# 3-HumiditySensor.net
KiCad netlist of a schematic drawn in Altium Designer
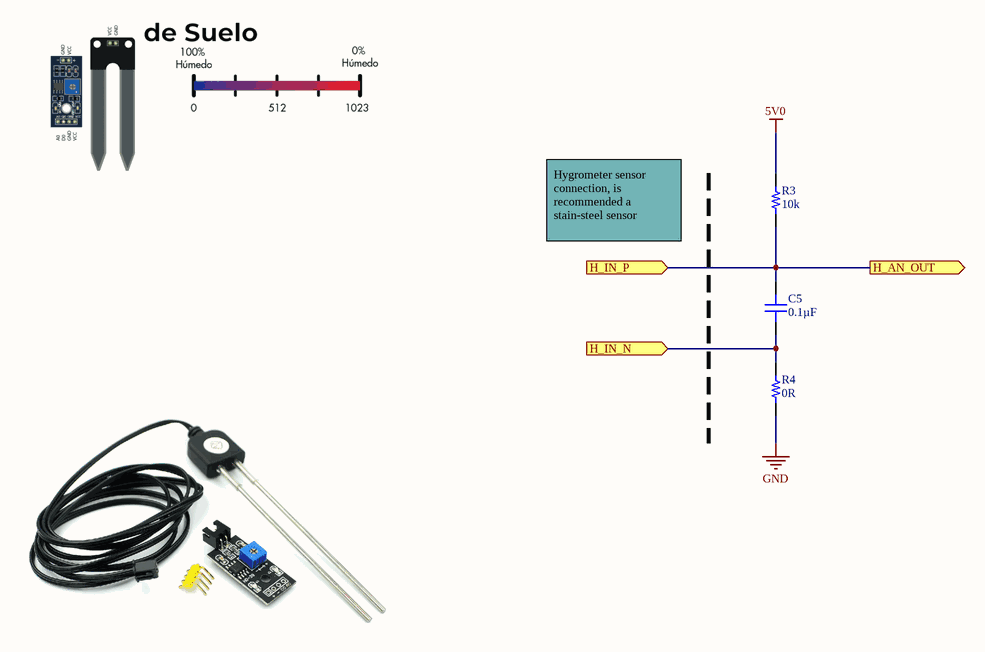
[diagram p0: 3-HumiditySensor.SchDoc]

(export (version "E")
  (design (tool "Eeschema 10.0.6"))
  (components
    (comp (ref "C5")
      (value "0.1µF")
      (footprint "CAP 0805_2012")
      (description "CAP CER 0.1UF 50V X7R 0805")
      (fields (field (name "PART NUMBER") "C0805C104M5RACAUTO") (field (name "MANUFACTURER") "KEMET"))
      (libsource (lib "Celestial Altium Library - altium_library") (part "Capacitor"))
    )
    (comp (ref "R3")
      (value "10k")
      (footprint "RES 0805_2012")
      (description "RES SMD 1.47K OHM 1% 1/8W 0805")
      (fields (field (name "PART NUMBER") "RC0805FR-071K47L") (field (name "MANUFACTURER") "Yageo"))
      (libsource (lib "Celestial Altium Library - altium_library") (part "Resistor"))
    )
    (comp (ref "R4")
      (value "0R")
      (footprint "RES 0805_2012")
      (description "RES SMD 1.47K OHM 1% 1/8W 0805")
      (fields (field (name "PART NUMBER") "RC0805FR-071K47L") (field (name "MANUFACTURER") "Yageo"))
      (libsource (lib "Celestial Altium Library - altium_library") (part "Resistor"))
    )
  )
  (nets
    (net (code "1") (name "/H_AN_OUT") (class "Default")
      (node (ref "C5") (pin "2") (pinfunction "2_2") (pintype "passive"))
      (node (ref "R3") (pin "1") (pinfunction "1_1") (pintype "passive"))
    )
    (net (code "2") (name "/H_IN_N") (class "Default")
      (node (ref "C5") (pin "1") (pinfunction "1_1") (pintype "passive"))
      (node (ref "R4") (pin "2") (pinfunction "2_2") (pintype "passive"))
    )
    (net (code "3") (name "5V0") (class "Default")
      (node (ref "R3") (pin "2") (pinfunction "2_2") (pintype "passive"))
    )
    (net (code "4") (name "GND") (class "Default")
      (node (ref "R4") (pin "1") (pinfunction "1_1") (pintype "passive"))
    )
  )
)
